# Main.net
KiCad netlist of a schematic drawn in EAGLE
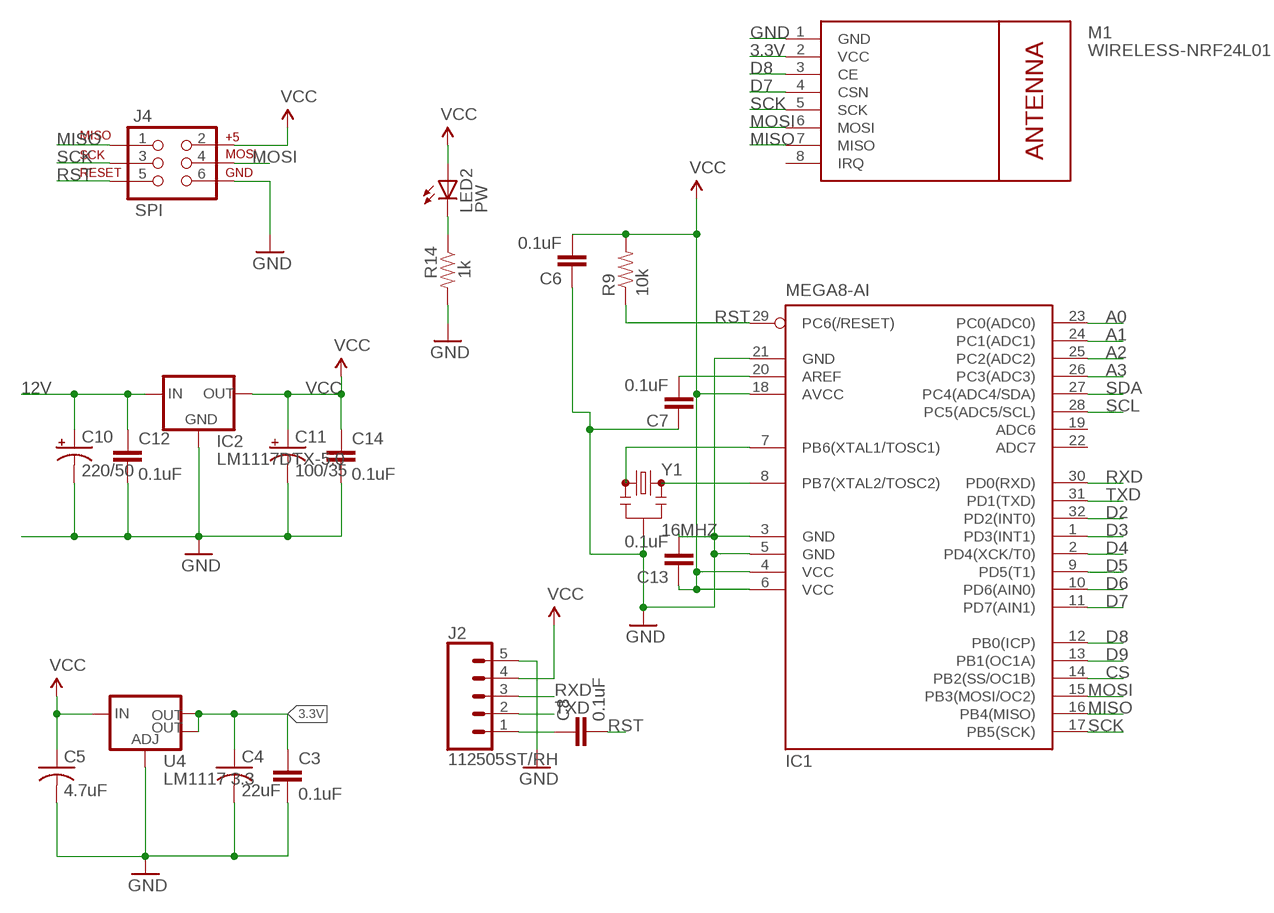
[diagram p0: schematic, sheet 1]

(export (version "E")
  (design (tool "Eeschema 10.0.6"))
  (components
    (comp (ref "C3")
      (value "0.1uF")
      (footprint "eagle-import:0805")
      (libsource (lib "eagle-import") (part "CAP0805"))
    )
    (comp (ref "C4")
      (value "22uF")
      (footprint "eagle-import:C1206")
      (libsource (lib "eagle-import") (part "C-USC1206"))
    )
    (comp (ref "C5")
      (value "4.7uF")
      (footprint "eagle-import:C1206")
      (libsource (lib "eagle-import") (part "C-USC1206"))
    )
    (comp (ref "C6")
      (value "0.1uF")
      (footprint "eagle-import:0805")
      (libsource (lib "eagle-import") (part "CAP0805"))
    )
    (comp (ref "C7")
      (value "0.1uF")
      (footprint "eagle-import:0805")
      (libsource (lib "eagle-import") (part "CAP0805"))
    )
    (comp (ref "C8")
      (value "0.1uF")
      (footprint "eagle-import:0805")
      (libsource (lib "eagle-import") (part "CAP0805"))
    )
    (comp (ref "C10")
      (value "220/50")
      (footprint "eagle-import:153CLV-1010")
      (libsource (lib "eagle-import") (part "CPOL-US153CLV-1010"))
    )
    (comp (ref "C11")
      (value "100/35")
      (footprint "eagle-import:153CLV-0605")
      (libsource (lib "eagle-import") (part "CPOL-US153CLV-0605"))
    )
    (comp (ref "C12")
      (value "0.1uF")
      (footprint "eagle-import:0805")
      (libsource (lib "eagle-import") (part "CAP0805"))
    )
    (comp (ref "C13")
      (value "0.1uF")
      (footprint "eagle-import:0805")
      (libsource (lib "eagle-import") (part "CAP0805"))
    )
    (comp (ref "C14")
      (value "0.1uF")
      (footprint "eagle-import:0805")
      (libsource (lib "eagle-import") (part "CAP0805"))
    )
    (comp (ref "IC1")
      (value "MEGA8-AI")
      (footprint "eagle-import:TQFP32-08")
      (fields (field (name "MPN") "ATMEGA8-16AU"))
      (libsource (lib "eagle-import") (part "MEGA8-AI"))
    )
    (comp (ref "IC2")
      (value "LM1117DTX-5.0")
      (footprint "eagle-import:TO252")
      (libsource (lib "eagle-import") (part "LM1117DTX-3.3"))
    )
    (comp (ref "J2")
      (value "112505ST/RH")
      (footprint "eagle-import:JST-5-PTH")
      (libsource (lib "eagle-import") (part "CONN_05JST"))
    )
    (comp (ref "J4")
      (value "SPI")
      (footprint "eagle-import:2X3")
      (libsource (lib "eagle-import") (part "AVR_SPI_PRG_6PTH"))
    )
    (comp (ref "LED2")
      (value "PW")
      (footprint "eagle-import:LED3MM")
      (libsource (lib "eagle-import") (part "LED3MM"))
    )
    (comp (ref "M1")
      (value "WIRELESS-NRF24L01")
      (footprint "eagle-import:WIRELESS-NRF24L01")
      (libsource (lib "eagle-import") (part "WIRELESS-NRF24L01"))
    )
    (comp (ref "R9")
      (value "10k")
      (footprint "eagle-import:0805")
      (libsource (lib "eagle-import") (part "RESISTOR0805-RES"))
    )
    (comp (ref "R14")
      (value "1k")
      (footprint "eagle-import:0805")
      (libsource (lib "eagle-import") (part "RESISTOR0805-RES"))
    )
    (comp (ref "U4")
      (value "LM1117 3.3")
      (footprint "eagle-import:SOT223")
      (libsource (lib "eagle-import") (part "V_REG_LM1117SOT223"))
    )
    (comp (ref "Y1")
      (value "16MHZ")
      (footprint "eagle-import:RESONATOR-SMD")
      (libsource (lib "eagle-import") (part "RESONATOR16MHZ"))
    )
  )
  (nets
    (net (code "1") (name "/12V") (class "Default")
      (node (ref "C10") (pin "+") (pinfunction "+_+") (pintype "passive"))
      (node (ref "C12") (pin "1") (pinfunction "1_1") (pintype "passive"))
      (node (ref "IC2") (pin "2") (pinfunction "IN_2") (pintype "input"))
    )
    (net (code "2") (name "/A0") (class "Default")
      (node (ref "IC1") (pin "23") (pinfunction "PC0(ADC0)_23") (pintype "bidirectional"))
    )
    (net (code "3") (name "/A1") (class "Default")
      (node (ref "IC1") (pin "24") (pinfunction "PC1(ADC1)_24") (pintype "bidirectional"))
    )
    (net (code "4") (name "/A2") (class "Default")
      (node (ref "IC1") (pin "25") (pinfunction "PC2(ADC2)_25") (pintype "bidirectional"))
    )
    (net (code "5") (name "/A3") (class "Default")
      (node (ref "IC1") (pin "26") (pinfunction "PC3(ADC3)_26") (pintype "bidirectional"))
    )
    (net (code "6") (name "/CS") (class "Default")
      (node (ref "IC1") (pin "14") (pinfunction "PB2(SS/OC1B)_14") (pintype "bidirectional"))
    )
    (net (code "7") (name "/D2") (class "Default")
      (node (ref "IC1") (pin "32") (pinfunction "PD2(INT0)_32") (pintype "bidirectional"))
    )
    (net (code "8") (name "/D3") (class "Default")
      (node (ref "IC1") (pin "1") (pinfunction "PD3(INT1)_1") (pintype "bidirectional"))
    )
    (net (code "9") (name "/D4") (class "Default")
      (node (ref "IC1") (pin "2") (pinfunction "PD4(XCK/T0)_2") (pintype "bidirectional"))
    )
    (net (code "10") (name "/D5") (class "Default")
      (node (ref "IC1") (pin "9") (pinfunction "PD5(T1)_9") (pintype "bidirectional"))
    )
    (net (code "11") (name "/D6") (class "Default")
      (node (ref "IC1") (pin "10") (pinfunction "PD6(AIN0)_10") (pintype "bidirectional"))
    )
    (net (code "12") (name "/D7") (class "Default")
      (node (ref "IC1") (pin "11") (pinfunction "PD7(AIN1)_11") (pintype "bidirectional"))
      (node (ref "M1") (pin "4") (pinfunction "CSN_4") (pintype "bidirectional"))
    )
    (net (code "13") (name "/D8") (class "Default")
      (node (ref "IC1") (pin "12") (pinfunction "PB0(ICP)_12") (pintype "bidirectional"))
      (node (ref "M1") (pin "3") (pinfunction "CE_3") (pintype "bidirectional"))
    )
    (net (code "14") (name "/D9") (class "Default")
      (node (ref "IC1") (pin "13") (pinfunction "PB1(OC1A)_13") (pintype "bidirectional"))
    )
    (net (code "15") (name "/MISO") (class "Default")
      (node (ref "IC1") (pin "16") (pinfunction "PB4(MISO)_16") (pintype "bidirectional"))
      (node (ref "J4") (pin "1") (pinfunction "1_1") (pintype "passive"))
      (node (ref "M1") (pin "7") (pinfunction "MISO_7") (pintype "bidirectional"))
    )
    (net (code "16") (name "/MOSI") (class "Default")
      (node (ref "IC1") (pin "15") (pinfunction "PB3(MOSI/OC2)_15") (pintype "bidirectional"))
      (node (ref "J4") (pin "4") (pinfunction "4_4") (pintype "passive"))
      (node (ref "M1") (pin "6") (pinfunction "MOSI_6") (pintype "bidirectional"))
    )
    (net (code "17") (name "/RST") (class "Default")
      (node (ref "C8") (pin "2") (pinfunction "2_2") (pintype "passive"))
      (node (ref "IC1") (pin "29") (pinfunction "PC6(/RESET)_29") (pintype "bidirectional"))
      (node (ref "J4") (pin "5") (pinfunction "5_5") (pintype "passive"))
      (node (ref "R9") (pin "1") (pinfunction "1_1") (pintype "passive"))
    )
    (net (code "18") (name "/RXD") (class "Default")
      (node (ref "IC1") (pin "30") (pinfunction "PD0(RXD)_30") (pintype "bidirectional"))
      (node (ref "J2") (pin "3") (pinfunction "3_3") (pintype "passive"))
    )
    (net (code "19") (name "/SCK") (class "Default")
      (node (ref "IC1") (pin "17") (pinfunction "PB5(SCK)_17") (pintype "bidirectional"))
      (node (ref "J4") (pin "3") (pinfunction "3_3") (pintype "passive"))
      (node (ref "M1") (pin "5") (pinfunction "SCK_5") (pintype "bidirectional"))
    )
    (net (code "20") (name "/SCL") (class "Default")
      (node (ref "IC1") (pin "28") (pinfunction "PC5(ADC5/SCL)_28") (pintype "bidirectional"))
    )
    (net (code "21") (name "/SDA") (class "Default")
      (node (ref "IC1") (pin "27") (pinfunction "PC4(ADC4/SDA)_27") (pintype "bidirectional"))
    )
    (net (code "22") (name "/TXD") (class "Default")
      (node (ref "IC1") (pin "31") (pinfunction "PD1(TXD)_31") (pintype "bidirectional"))
      (node (ref "J2") (pin "2") (pinfunction "2_2") (pintype "passive"))
    )
    (net (code "23") (name "3.3V") (class "Default")
      (node (ref "C3") (pin "1") (pinfunction "1_1") (pintype "passive"))
      (node (ref "C4") (pin "1") (pinfunction "1_1") (pintype "passive"))
      (node (ref "M1") (pin "2") (pinfunction "VCC_2") (pintype "power_in"))
      (node (ref "U4") (pin "2") (pinfunction "OUT_2") (pintype "output"))
      (node (ref "U4") (pin "4") (pinfunction "OUT_4") (pintype "output"))
    )
    (net (code "24") (name "GND") (class "Default")
      (node (ref "C10") (pin "-") (pinfunction "-_-") (pintype "passive"))
      (node (ref "C11") (pin "-") (pinfunction "-_-") (pintype "passive"))
      (node (ref "C12") (pin "2") (pinfunction "2_2") (pintype "passive"))
      (node (ref "C13") (pin "2") (pinfunction "2_2") (pintype "passive"))
      (node (ref "C14") (pin "2") (pinfunction "2_2") (pintype "passive"))
      (node (ref "C3") (pin "2") (pinfunction "2_2") (pintype "passive"))
      (node (ref "C4") (pin "2") (pinfunction "2_2") (pintype "passive"))
      (node (ref "C5") (pin "2") (pinfunction "2_2") (pintype "passive"))
      (node (ref "C6") (pin "1") (pinfunction "1_1") (pintype "passive"))
      (node (ref "C7") (pin "1") (pinfunction "1_1") (pintype "passive"))
      (node (ref "IC1") (pin "21") (pinfunction "GND_21") (pintype "power_in"))
      (node (ref "IC1") (pin "3") (pinfunction "GND_3") (pintype "power_in"))
      (node (ref "IC1") (pin "5") (pinfunction "GND_5") (pintype "power_in"))
      (node (ref "IC2") (pin "1") (pinfunction "GND_1") (pintype "input"))
      (node (ref "J2") (pin "5") (pinfunction "5_5") (pintype "passive"))
      (node (ref "J4") (pin "6") (pinfunction "6_6") (pintype "passive"))
      (node (ref "M1") (pin "1") (pinfunction "GND_1") (pintype "power_in"))
      (node (ref "R14") (pin "2") (pinfunction "2_2") (pintype "passive"))
      (node (ref "U4") (pin "1") (pinfunction "ADJ_1") (pintype "input"))
      (node (ref "Y1") (pin "2") (pinfunction "2_2") (pintype "passive"))
    )
    (net (code "25") (name "Net-(C8-Pad1)") (class "Default")
      (node (ref "C8") (pin "1") (pinfunction "1_1") (pintype "passive"))
      (node (ref "J2") (pin "1") (pinfunction "1_1") (pintype "passive"))
    )
    (net (code "26") (name "Net-(IC1-AREF)") (class "Default")
      (node (ref "C7") (pin "2") (pinfunction "2_2") (pintype "passive"))
      (node (ref "IC1") (pin "20") (pinfunction "AREF_20") (pintype "passive"))
    )
    (net (code "27") (name "Net-(IC1-PB6(XTAL1{slash}TOSC1))") (class "Default")
      (node (ref "IC1") (pin "7") (pinfunction "PB6(XTAL1/TOSC1)_7") (pintype "bidirectional"))
      (node (ref "Y1") (pin "1") (pinfunction "1_1") (pintype "passive"))
    )
    (net (code "28") (name "Net-(IC1-PB7(XTAL2{slash}TOSC2))") (class "Default")
      (node (ref "IC1") (pin "8") (pinfunction "PB7(XTAL2/TOSC2)_8") (pintype "bidirectional"))
      (node (ref "Y1") (pin "3") (pinfunction "3_3") (pintype "passive"))
    )
    (net (code "29") (name "Net-(LED2-C)") (class "Default")
      (node (ref "LED2") (pin "K") (pinfunction "C_K") (pintype "passive"))
      (node (ref "R14") (pin "1") (pinfunction "1_1") (pintype "passive"))
    )
    (net (code "30") (name "VCC") (class "Default")
      (node (ref "C11") (pin "+") (pinfunction "+_+") (pintype "passive"))
      (node (ref "C13") (pin "1") (pinfunction "1_1") (pintype "passive"))
      (node (ref "C14") (pin "1") (pinfunction "1_1") (pintype "passive"))
      (node (ref "C5") (pin "1") (pinfunction "1_1") (pintype "passive"))
      (node (ref "C6") (pin "2") (pinfunction "2_2") (pintype "passive"))
      (node (ref "IC1") (pin "18") (pinfunction "AVCC_18") (pintype "power_in"))
      (node (ref "IC1") (pin "4") (pinfunction "VCC_4") (pintype "power_in"))
      (node (ref "IC1") (pin "6") (pinfunction "VCC_6") (pintype "power_in"))
      (node (ref "IC2") (pin "TAB") (pinfunction "OUT_TAB") (pintype "passive"))
      (node (ref "J2") (pin "4") (pinfunction "4_4") (pintype "passive"))
      (node (ref "J4") (pin "2") (pinfunction "2_2") (pintype "passive"))
      (node (ref "LED2") (pin "A") (pinfunction "A_A") (pintype "passive"))
      (node (ref "R9") (pin "2") (pinfunction "2_2") (pintype "passive"))
      (node (ref "U4") (pin "3") (pinfunction "IN_3") (pintype "input"))
    )
    (net (code "31") (name "unconnected-(IC1-ADC6-Pad19)") (class "Default")
      (node (ref "IC1") (pin "19") (pinfunction "ADC6_19") (pintype "bidirectional"))
    )
    (net (code "32") (name "unconnected-(IC1-ADC7-Pad22)") (class "Default")
      (node (ref "IC1") (pin "22") (pinfunction "ADC7_22") (pintype "bidirectional"))
    )
    (net (code "33") (name "unconnected-(M1-IRQ-Pad8)") (class "Default")
      (node (ref "M1") (pin "8") (pinfunction "IRQ_8") (pintype "bidirectional"))
    )
  )
)
